# MPU-Power.net
KiCad netlist of a schematic drawn in Altium Designer
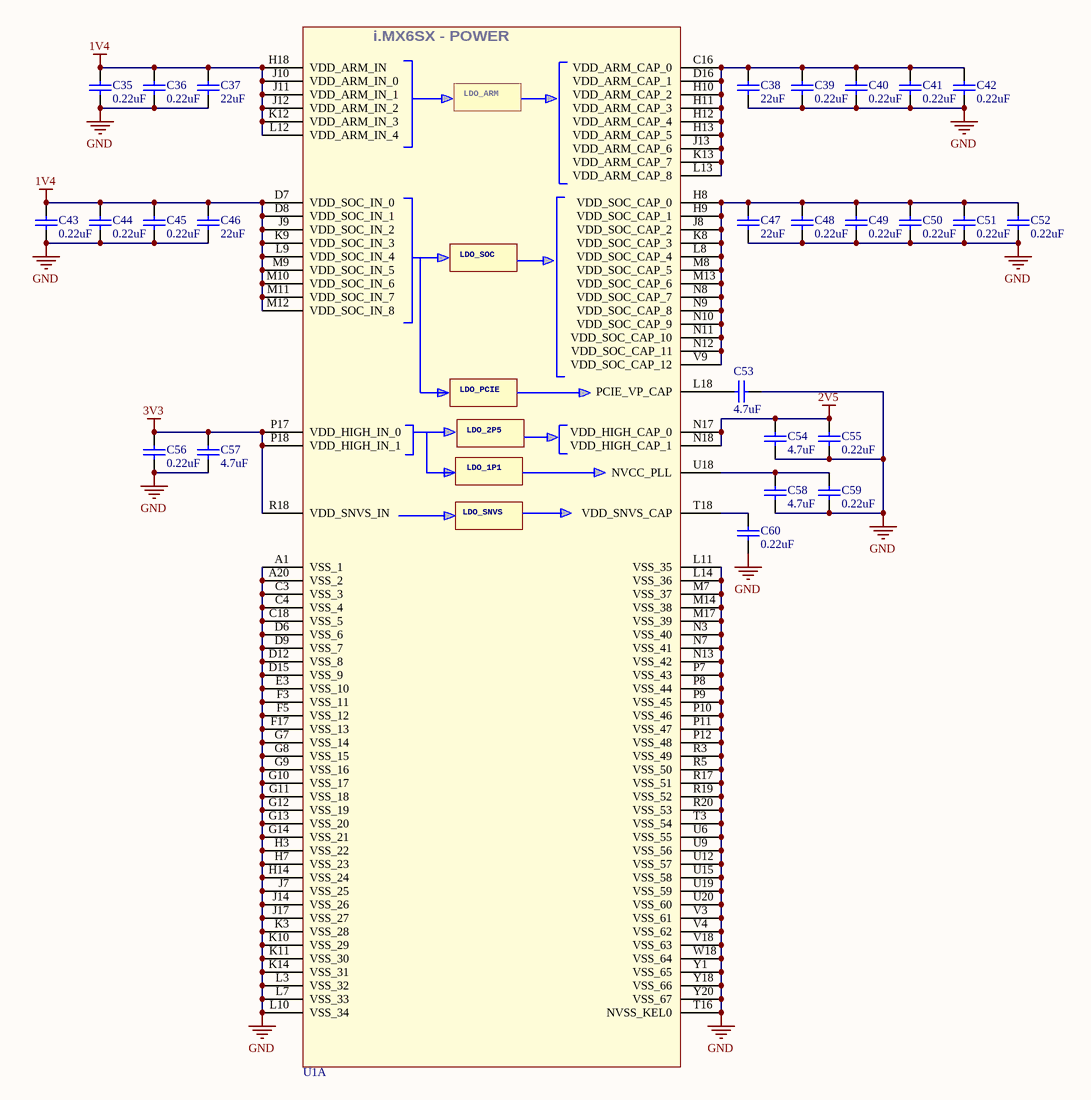
[diagram p0: MPU-Power.SchDoc]

(export (version "E")
  (design (tool "Eeschema 10.0.6"))
  (components
    (comp (ref "C35")
      (value "0.22uF")
      (footprint "C0402[1005X55]")
      (description "0.22uF 6.3V 10% 0402 (1005 Metric)")
      (fields (field (name "PARTNUMBER") "JMK105BJ224KV-F") (field (name "MANUFACTURER") "Taiyo Yuden"))
      (libsource (lib "Capacitors") (part "CAP_0.22uF_6.3V_0402_10%"))
    )
    (comp (ref "C36")
      (value "0.22uF")
      (footprint "C0402[1005X55]")
      (description "0.22uF 6.3V 10% 0402 (1005 Metric)")
      (fields (field (name "PARTNUMBER") "JMK105BJ224KV-F") (field (name "MANUFACTURER") "Taiyo Yuden"))
      (libsource (lib "Capacitors") (part "CAP_0.22uF_6.3V_0402_10%"))
    )
    (comp (ref "C37")
      (value "22uF")
      (footprint "C0603[1608X92]")
      (description "22uF 6.3V 10% 0603 (1608 Metric)")
      (fields (field (name "PARTNUMBER") "GRT188R60J226ME13D") (field (name "MANUFACTURER") "Murata"))
      (libsource (lib "Capacitors") (part "CAP_22uF_6.3V_0603_10%"))
    )
    (comp (ref "C38")
      (value "22uF")
      (footprint "C0603[1608X92]")
      (description "22uF 6.3V 10% 0603 (1608 Metric)")
      (fields (field (name "PARTNUMBER") "GRT188R60J226ME13D") (field (name "MANUFACTURER") "Murata"))
      (libsource (lib "Capacitors") (part "CAP_22uF_6.3V_0603_10%"))
    )
    (comp (ref "C39")
      (value "0.22uF")
      (footprint "C0402[1005X55]")
      (description "0.22uF 6.3V 10% 0402 (1005 Metric)")
      (fields (field (name "PARTNUMBER") "JMK105BJ224KV-F") (field (name "MANUFACTURER") "Taiyo Yuden"))
      (libsource (lib "Capacitors") (part "CAP_0.22uF_6.3V_0402_10%"))
    )
    (comp (ref "C40")
      (value "0.22uF")
      (footprint "C0402[1005X55]")
      (description "0.22uF 6.3V 10% 0402 (1005 Metric)")
      (fields (field (name "PARTNUMBER") "JMK105BJ224KV-F") (field (name "MANUFACTURER") "Taiyo Yuden"))
      (libsource (lib "Capacitors") (part "CAP_0.22uF_6.3V_0402_10%"))
    )
    (comp (ref "C41")
      (value "0.22uF")
      (footprint "C0402[1005X55]")
      (description "0.22uF 6.3V 10% 0402 (1005 Metric)")
      (fields (field (name "PARTNUMBER") "JMK105BJ224KV-F") (field (name "MANUFACTURER") "Taiyo Yuden"))
      (libsource (lib "Capacitors") (part "CAP_0.22uF_6.3V_0402_10%"))
    )
    (comp (ref "C42")
      (value "0.22uF")
      (footprint "C0402[1005X55]")
      (description "0.22uF 6.3V 10% 0402 (1005 Metric)")
      (fields (field (name "PARTNUMBER") "JMK105BJ224KV-F") (field (name "MANUFACTURER") "Taiyo Yuden"))
      (libsource (lib "Capacitors") (part "CAP_0.22uF_6.3V_0402_10%"))
    )
    (comp (ref "C43")
      (value "0.22uF")
      (footprint "C0402[1005X55]")
      (description "0.22uF 6.3V 10% 0402 (1005 Metric)")
      (fields (field (name "PARTNUMBER") "JMK105BJ224KV-F") (field (name "MANUFACTURER") "Taiyo Yuden"))
      (libsource (lib "Capacitors") (part "CAP_0.22uF_6.3V_0402_10%"))
    )
    (comp (ref "C44")
      (value "0.22uF")
      (footprint "C0402[1005X55]")
      (description "0.22uF 6.3V 10% 0402 (1005 Metric)")
      (fields (field (name "PARTNUMBER") "JMK105BJ224KV-F") (field (name "MANUFACTURER") "Taiyo Yuden"))
      (libsource (lib "Capacitors") (part "CAP_0.22uF_6.3V_0402_10%"))
    )
    (comp (ref "C45")
      (value "0.22uF")
      (footprint "C0402[1005X55]")
      (description "0.22uF 6.3V 10% 0402 (1005 Metric)")
      (fields (field (name "PARTNUMBER") "JMK105BJ224KV-F") (field (name "MANUFACTURER") "Taiyo Yuden"))
      (libsource (lib "Capacitors") (part "CAP_0.22uF_6.3V_0402_10%"))
    )
    (comp (ref "C46")
      (value "22uF")
      (footprint "C0603[1608X92]")
      (description "22uF 6.3V 10% 0603 (1608 Metric)")
      (fields (field (name "PARTNUMBER") "GRT188R60J226ME13D") (field (name "MANUFACTURER") "Murata"))
      (libsource (lib "Capacitors") (part "CAP_22uF_6.3V_0603_10%"))
    )
    (comp (ref "C47")
      (value "22uF")
      (footprint "C0603[1608X92]")
      (description "22uF 6.3V 10% 0603 (1608 Metric)")
      (fields (field (name "PARTNUMBER") "GRT188R60J226ME13D") (field (name "MANUFACTURER") "Murata"))
      (libsource (lib "Capacitors") (part "CAP_22uF_6.3V_0603_10%"))
    )
    (comp (ref "C48")
      (value "0.22uF")
      (footprint "C0402[1005X55]")
      (description "0.22uF 6.3V 10% 0402 (1005 Metric)")
      (fields (field (name "PARTNUMBER") "JMK105BJ224KV-F") (field (name "MANUFACTURER") "Taiyo Yuden"))
      (libsource (lib "Capacitors") (part "CAP_0.22uF_6.3V_0402_10%"))
    )
    (comp (ref "C49")
      (value "0.22uF")
      (footprint "C0402[1005X55]")
      (description "0.22uF 6.3V 10% 0402 (1005 Metric)")
      (fields (field (name "PARTNUMBER") "JMK105BJ224KV-F") (field (name "MANUFACTURER") "Taiyo Yuden"))
      (libsource (lib "Capacitors") (part "CAP_0.22uF_6.3V_0402_10%"))
    )
    (comp (ref "C50")
      (value "0.22uF")
      (footprint "C0402[1005X55]")
      (description "0.22uF 6.3V 10% 0402 (1005 Metric)")
      (fields (field (name "PARTNUMBER") "JMK105BJ224KV-F") (field (name "MANUFACTURER") "Taiyo Yuden"))
      (libsource (lib "Capacitors") (part "CAP_0.22uF_6.3V_0402_10%"))
    )
    (comp (ref "C51")
      (value "0.22uF")
      (footprint "C0402[1005X55]")
      (description "0.22uF 6.3V 10% 0402 (1005 Metric)")
      (fields (field (name "PARTNUMBER") "JMK105BJ224KV-F") (field (name "MANUFACTURER") "Taiyo Yuden"))
      (libsource (lib "Capacitors") (part "CAP_0.22uF_6.3V_0402_10%"))
    )
    (comp (ref "C52")
      (value "0.22uF")
      (footprint "C0402[1005X55]")
      (description "0.22uF 6.3V 10% 0402 (1005 Metric)")
      (fields (field (name "PARTNUMBER") "JMK105BJ224KV-F") (field (name "MANUFACTURER") "Taiyo Yuden"))
      (libsource (lib "Capacitors") (part "CAP_0.22uF_6.3V_0402_10%"))
    )
    (comp (ref "C53")
      (value "4.7uF")
      (footprint "C0402[1005X55]")
      (description "4.7uF 6.3V 20% 0402 (1005 Metric)")
      (fields (field (name "PARTNUMBER") "GRM155R60J475ME47D") (field (name "MANUFACTURER") "Murata"))
      (libsource (lib "Capacitors") (part "CAP_4.7uF_6.3V_0402_20%"))
    )
    (comp (ref "C54")
      (value "4.7uF")
      (footprint "C0402[1005X55]")
      (description "4.7uF 6.3V 20% 0402 (1005 Metric)")
      (fields (field (name "PARTNUMBER") "GRM155R60J475ME47D") (field (name "MANUFACTURER") "Murata"))
      (libsource (lib "Capacitors") (part "CAP_4.7uF_6.3V_0402_20%"))
    )
    (comp (ref "C55")
      (value "0.22uF")
      (footprint "C0402[1005X55]")
      (description "0.22uF 6.3V 10% 0402 (1005 Metric)")
      (fields (field (name "PARTNUMBER") "JMK105BJ224KV-F") (field (name "MANUFACTURER") "Taiyo Yuden"))
      (libsource (lib "Capacitors") (part "CAP_0.22uF_6.3V_0402_10%"))
    )
    (comp (ref "C56")
      (value "0.22uF")
      (footprint "C0402[1005X55]")
      (description "0.22uF 6.3V 10% 0402 (1005 Metric)")
      (fields (field (name "PARTNUMBER") "JMK105BJ224KV-F") (field (name "MANUFACTURER") "Taiyo Yuden"))
      (libsource (lib "Capacitors") (part "CAP_0.22uF_6.3V_0402_10%"))
    )
    (comp (ref "C57")
      (value "4.7uF")
      (footprint "C0402[1005X55]")
      (description "4.7uF 6.3V 20% 0402 (1005 Metric)")
      (fields (field (name "PARTNUMBER") "GRM155R60J475ME47D") (field (name "MANUFACTURER") "Murata"))
      (libsource (lib "Capacitors") (part "CAP_4.7uF_6.3V_0402_20%"))
    )
    (comp (ref "C58")
      (value "4.7uF")
      (footprint "C0402[1005X55]")
      (description "4.7uF 6.3V 20% 0402 (1005 Metric)")
      (fields (field (name "PARTNUMBER") "GRM155R60J475ME47D") (field (name "MANUFACTURER") "Murata"))
      (libsource (lib "Capacitors") (part "CAP_4.7uF_6.3V_0402_20%"))
    )
    (comp (ref "C59")
      (value "0.22uF")
      (footprint "C0402[1005X55]")
      (description "0.22uF 6.3V 10% 0402 (1005 Metric)")
      (fields (field (name "PARTNUMBER") "JMK105BJ224KV-F") (field (name "MANUFACTURER") "Taiyo Yuden"))
      (libsource (lib "Capacitors") (part "CAP_0.22uF_6.3V_0402_10%"))
    )
    (comp (ref "C60")
      (value "0.22uF")
      (footprint "C0402[1005X55]")
      (description "0.22uF 6.3V 10% 0402 (1005 Metric)")
      (fields (field (name "PARTNUMBER") "JMK105BJ224KV-F") (field (name "MANUFACTURER") "Taiyo Yuden"))
      (libsource (lib "Capacitors") (part "CAP_0.22uF_6.3V_0402_10%"))
    )
    (comp (ref "U1")
      (value "MCIMX6X3EVO10AB")
      (footprint "BGA-400")
      (description "IC MPU I.MX6SX 1GHZ 400MAPBGA")
      (fields (field (name "MANUFACTURER") "NXP"))
      (libsource (lib "ICs") (part "MCIMX6X3EVO10AB"))
    )
  )
  (nets
    (net (code "1") (name "1V4") (class "Default")
      (node (ref "C35") (pin "2") (pinfunction "2_2") (pintype "passive"))
      (node (ref "C36") (pin "2") (pinfunction "2_2") (pintype "passive"))
      (node (ref "C37") (pin "2") (pinfunction "2_2") (pintype "passive"))
      (node (ref "C43") (pin "2") (pinfunction "2_2") (pintype "passive"))
      (node (ref "C44") (pin "2") (pinfunction "2_2") (pintype "passive"))
      (node (ref "C45") (pin "2") (pinfunction "2_2") (pintype "passive"))
      (node (ref "C46") (pin "2") (pinfunction "2_2") (pintype "passive"))
      (node (ref "U1") (pin "D7") (pinfunction "VDD_SOC_IN_0_D7") (pintype "power_in"))
      (node (ref "U1") (pin "D8") (pinfunction "VDD_SOC_IN_1_D8") (pintype "power_in"))
      (node (ref "U1") (pin "H18") (pinfunction "VDD_ARM_IN_H18") (pintype "power_in"))
      (node (ref "U1") (pin "J10") (pinfunction "VDD_ARM_IN_0_J10") (pintype "power_in"))
      (node (ref "U1") (pin "J11") (pinfunction "VDD_ARM_IN_1_J11") (pintype "power_in"))
      (node (ref "U1") (pin "J12") (pinfunction "VDD_ARM_IN_2_J12") (pintype "power_in"))
      (node (ref "U1") (pin "J9") (pinfunction "VDD_SOC_IN_2_J9") (pintype "power_in"))
      (node (ref "U1") (pin "K12") (pinfunction "VDD_ARM_IN_3_K12") (pintype "power_in"))
      (node (ref "U1") (pin "K9") (pinfunction "VDD_SOC_IN_3_K9") (pintype "power_in"))
      (node (ref "U1") (pin "L12") (pinfunction "VDD_ARM_IN_4_L12") (pintype "power_in"))
      (node (ref "U1") (pin "L9") (pinfunction "VDD_SOC_IN_4_L9") (pintype "power_in"))
      (node (ref "U1") (pin "M10") (pinfunction "VDD_SOC_IN_6_M10") (pintype "power_in"))
      (node (ref "U1") (pin "M11") (pinfunction "VDD_SOC_IN_7_M11") (pintype "power_in"))
      (node (ref "U1") (pin "M12") (pinfunction "VDD_SOC_IN_8_M12") (pintype "power_in"))
      (node (ref "U1") (pin "M9") (pinfunction "VDD_SOC_IN_5_M9") (pintype "power_in"))
    )
    (net (code "2") (name "2V5") (class "Default")
      (node (ref "C54") (pin "2") (pinfunction "2_2") (pintype "passive"))
      (node (ref "C55") (pin "2") (pinfunction "2_2") (pintype "passive"))
      (node (ref "U1") (pin "N17") (pinfunction "VDD_HIGH_CAP_0_N17") (pintype "power_in"))
      (node (ref "U1") (pin "N18") (pinfunction "VDD_HIGH_CAP_1_N18") (pintype "power_in"))
    )
    (net (code "3") (name "3V3") (class "Default")
      (node (ref "C56") (pin "2") (pinfunction "2_2") (pintype "passive"))
      (node (ref "C57") (pin "2") (pinfunction "2_2") (pintype "passive"))
      (node (ref "U1") (pin "P17") (pinfunction "VDD_HIGH_IN_0_P17") (pintype "power_in"))
      (node (ref "U1") (pin "P18") (pinfunction "VDD_HIGH_IN_1_P18") (pintype "power_in"))
      (node (ref "U1") (pin "R18") (pinfunction "VDD_SNVS_IN_R18") (pintype "power_in"))
    )
    (net (code "4") (name "GND") (class "Default")
      (node (ref "C35") (pin "1") (pinfunction "1_1") (pintype "passive"))
      (node (ref "C36") (pin "1") (pinfunction "1_1") (pintype "passive"))
      (node (ref "C37") (pin "1") (pinfunction "1_1") (pintype "passive"))
      (node (ref "C38") (pin "1") (pinfunction "1_1") (pintype "passive"))
      (node (ref "C39") (pin "1") (pinfunction "1_1") (pintype "passive"))
      (node (ref "C40") (pin "1") (pinfunction "1_1") (pintype "passive"))
      (node (ref "C41") (pin "1") (pinfunction "1_1") (pintype "passive"))
      (node (ref "C42") (pin "1") (pinfunction "1_1") (pintype "passive"))
      (node (ref "C43") (pin "1") (pinfunction "1_1") (pintype "passive"))
      (node (ref "C44") (pin "1") (pinfunction "1_1") (pintype "passive"))
      (node (ref "C45") (pin "1") (pinfunction "1_1") (pintype "passive"))
      (node (ref "C46") (pin "1") (pinfunction "1_1") (pintype "passive"))
      (node (ref "C47") (pin "1") (pinfunction "1_1") (pintype "passive"))
      (node (ref "C48") (pin "1") (pinfunction "1_1") (pintype "passive"))
      (node (ref "C49") (pin "1") (pinfunction "1_1") (pintype "passive"))
      (node (ref "C50") (pin "1") (pinfunction "1_1") (pintype "passive"))
      (node (ref "C51") (pin "1") (pinfunction "1_1") (pintype "passive"))
      (node (ref "C52") (pin "1") (pinfunction "1_1") (pintype "passive"))
      (node (ref "C53") (pin "1") (pinfunction "1_1") (pintype "passive"))
      (node (ref "C54") (pin "1") (pinfunction "1_1") (pintype "passive"))
      (node (ref "C55") (pin "1") (pinfunction "1_1") (pintype "passive"))
      (node (ref "C56") (pin "1") (pinfunction "1_1") (pintype "passive"))
      (node (ref "C57") (pin "1") (pinfunction "1_1") (pintype "passive"))
      (node (ref "C58") (pin "1") (pinfunction "1_1") (pintype "passive"))
      (node (ref "C59") (pin "1") (pinfunction "1_1") (pintype "passive"))
      (node (ref "C60") (pin "1") (pinfunction "1_1") (pintype "passive"))
      (node (ref "U1") (pin "A1") (pinfunction "VSS_1_A1") (pintype "power_in"))
      (node (ref "U1") (pin "A20") (pinfunction "VSS_2_A20") (pintype "power_in"))
      (node (ref "U1") (pin "C18") (pinfunction "VSS_5_C18") (pintype "power_in"))
      (node (ref "U1") (pin "C3") (pinfunction "VSS_3_C3") (pintype "power_in"))
      (node (ref "U1") (pin "C4") (pinfunction "VSS_4_C4") (pintype "power_in"))
      (node (ref "U1") (pin "D12") (pinfunction "VSS_8_D12") (pintype "power_in"))
      (node (ref "U1") (pin "D15") (pinfunction "VSS_9_D15") (pintype "power_in"))
      (node (ref "U1") (pin "D6") (pinfunction "VSS_6_D6") (pintype "power_in"))
      (node (ref "U1") (pin "D9") (pinfunction "VSS_7_D9") (pintype "power_in"))
      (node (ref "U1") (pin "E3") (pinfunction "VSS_10_E3") (pintype "power_in"))
      (node (ref "U1") (pin "F17") (pinfunction "VSS_13_F17") (pintype "power_in"))
      (node (ref "U1") (pin "F3") (pinfunction "VSS_11_F3") (pintype "power_in"))
      (node (ref "U1") (pin "F5") (pinfunction "VSS_12_F5") (pintype "power_in"))
      (node (ref "U1") (pin "G10") (pinfunction "VSS_17_G10") (pintype "power_in"))
      (node (ref "U1") (pin "G11") (pinfunction "VSS_18_G11") (pintype "power_in"))
      (node (ref "U1") (pin "G12") (pinfunction "VSS_19_G12") (pintype "power_in"))
      (node (ref "U1") (pin "G13") (pinfunction "VSS_20_G13") (pintype "power_in"))
      (node (ref "U1") (pin "G14") (pinfunction "VSS_21_G14") (pintype "power_in"))
      (node (ref "U1") (pin "G7") (pinfunction "VSS_14_G7") (pintype "power_in"))
      (node (ref "U1") (pin "G8") (pinfunction "VSS_15_G8") (pintype "power_in"))
      (node (ref "U1") (pin "G9") (pinfunction "VSS_16_G9") (pintype "power_in"))
      (node (ref "U1") (pin "H14") (pinfunction "VSS_24_H14") (pintype "power_in"))
      (node (ref "U1") (pin "H3") (pinfunction "VSS_22_H3") (pintype "power_in"))
      (node (ref "U1") (pin "H7") (pinfunction "VSS_23_H7") (pintype "power_in"))
      (node (ref "U1") (pin "J14") (pinfunction "VSS_26_J14") (pintype "power_in"))
      (node (ref "U1") (pin "J17") (pinfunction "VSS_27_J17") (pintype "power_in"))
      (node (ref "U1") (pin "J7") (pinfunction "VSS_25_J7") (pintype "power_in"))
      (node (ref "U1") (pin "K10") (pinfunction "VSS_29_K10") (pintype "power_in"))
      (node (ref "U1") (pin "K11") (pinfunction "VSS_30_K11") (pintype "power_in"))
      (node (ref "U1") (pin "K14") (pinfunction "VSS_31_K14") (pintype "power_in"))
      (node (ref "U1") (pin "K3") (pinfunction "VSS_28_K3") (pintype "power_in"))
      (node (ref "U1") (pin "L10") (pinfunction "VSS_34_L10") (pintype "power_in"))
      (node (ref "U1") (pin "L11") (pinfunction "VSS_35_L11") (pintype "power_in"))
      (node (ref "U1") (pin "L14") (pinfunction "VSS_36_L14") (pintype "power_in"))
      (node (ref "U1") (pin "L3") (pinfunction "VSS_32_L3") (pintype "power_in"))
      (node (ref "U1") (pin "L7") (pinfunction "VSS_33_L7") (pintype "power_in"))
      (node (ref "U1") (pin "M14") (pinfunction "VSS_38_M14") (pintype "power_in"))
      (node (ref "U1") (pin "M17") (pinfunction "VSS_39_M17") (pintype "power_in"))
      (node (ref "U1") (pin "M7") (pinfunction "VSS_37_M7") (pintype "power_in"))
      (node (ref "U1") (pin "N13") (pinfunction "VSS_42_N13") (pintype "power_in"))
      (node (ref "U1") (pin "N3") (pinfunction "VSS_40_N3") (pintype "power_in"))
      (node (ref "U1") (pin "N7") (pinfunction "VSS_41_N7") (pintype "power_in"))
      (node (ref "U1") (pin "P10") (pinfunction "VSS_46_P10") (pintype "power_in"))
      (node (ref "U1") (pin "P11") (pinfunction "VSS_47_P11") (pintype "power_in"))
      (node (ref "U1") (pin "P12") (pinfunction "VSS_48_P12") (pintype "power_in"))
      (node (ref "U1") (pin "P7") (pinfunction "VSS_43_P7") (pintype "power_in"))
      (node (ref "U1") (pin "P8") (pinfunction "VSS_44_P8") (pintype "power_in"))
      (node (ref "U1") (pin "P9") (pinfunction "VSS_45_P9") (pintype "power_in"))
      (node (ref "U1") (pin "R17") (pinfunction "VSS_51_R17") (pintype "power_in"))
      (node (ref "U1") (pin "R19") (pinfunction "VSS_52_R19") (pintype "power_in"))
      (node (ref "U1") (pin "R20") (pinfunction "VSS_53_R20") (pintype "power_in"))
      (node (ref "U1") (pin "R3") (pinfunction "VSS_49_R3") (pintype "power_in"))
      (node (ref "U1") (pin "R5") (pinfunction "VSS_50_R5") (pintype "power_in"))
      (node (ref "U1") (pin "T16") (pinfunction "NVSS_KEL0_T16") (pintype "power_in"))
      (node (ref "U1") (pin "T3") (pinfunction "VSS_54_T3") (pintype "power_in"))
      (node (ref "U1") (pin "U12") (pinfunction "VSS_57_U12") (pintype "power_in"))
      (node (ref "U1") (pin "U15") (pinfunction "VSS_58_U15") (pintype "power_in"))
      (node (ref "U1") (pin "U19") (pinfunction "VSS_59_U19") (pintype "power_in"))
      (node (ref "U1") (pin "U20") (pinfunction "VSS_60_U20") (pintype "power_in"))
      (node (ref "U1") (pin "U6") (pinfunction "VSS_55_U6") (pintype "power_in"))
      (node (ref "U1") (pin "U9") (pinfunction "VSS_56_U9") (pintype "power_in"))
      (node (ref "U1") (pin "V18") (pinfunction "VSS_63_V18") (pintype "power_in"))
      (node (ref "U1") (pin "V3") (pinfunction "VSS_61_V3") (pintype "power_in"))
      (node (ref "U1") (pin "V4") (pinfunction "VSS_62_V4") (pintype "power_in"))
      (node (ref "U1") (pin "W18") (pinfunction "VSS_64_W18") (pintype "power_in"))
      (node (ref "U1") (pin "Y1") (pinfunction "VSS_65_Y1") (pintype "power_in"))
      (node (ref "U1") (pin "Y18") (pinfunction "VSS_66_Y18") (pintype "power_in"))
      (node (ref "U1") (pin "Y20") (pinfunction "VSS_67_Y20") (pintype "power_in"))
    )
    (net (code "5") (name "Net-(U1A-NVCC_PLL)") (class "Default")
      (node (ref "C58") (pin "2") (pinfunction "2_2") (pintype "passive"))
      (node (ref "C59") (pin "2") (pinfunction "2_2") (pintype "passive"))
      (node (ref "U1") (pin "U18") (pinfunction "NVCC_PLL_U18") (pintype "power_in"))
    )
    (net (code "6") (name "Net-(U1A-PCIE_VP_CAP)") (class "Default")
      (node (ref "C53") (pin "2") (pinfunction "2_2") (pintype "passive"))
      (node (ref "U1") (pin "L18") (pinfunction "PCIE_VP_CAP_L18") (pintype "power_in"))
    )
    (net (code "7") (name "Net-(U1A-VDD_ARM_CAP_0)") (class "Default")
      (node (ref "C38") (pin "2") (pinfunction "2_2") (pintype "passive"))
      (node (ref "C39") (pin "2") (pinfunction "2_2") (pintype "passive"))
      (node (ref "C40") (pin "2") (pinfunction "2_2") (pintype "passive"))
      (node (ref "C41") (pin "2") (pinfunction "2_2") (pintype "passive"))
      (node (ref "C42") (pin "2") (pinfunction "2_2") (pintype "passive"))
      (node (ref "U1") (pin "C16") (pinfunction "VDD_ARM_CAP_0_C16") (pintype "power_in"))
      (node (ref "U1") (pin "D16") (pinfunction "VDD_ARM_CAP_1_D16") (pintype "power_in"))
      (node (ref "U1") (pin "H10") (pinfunction "VDD_ARM_CAP_2_H10") (pintype "power_in"))
      (node (ref "U1") (pin "H11") (pinfunction "VDD_ARM_CAP_3_H11") (pintype "power_in"))
      (node (ref "U1") (pin "H12") (pinfunction "VDD_ARM_CAP_4_H12") (pintype "power_in"))
      (node (ref "U1") (pin "H13") (pinfunction "VDD_ARM_CAP_5_H13") (pintype "power_in"))
      (node (ref "U1") (pin "J13") (pinfunction "VDD_ARM_CAP_6_J13") (pintype "power_in"))
      (node (ref "U1") (pin "K13") (pinfunction "VDD_ARM_CAP_7_K13") (pintype "power_in"))
      (node (ref "U1") (pin "L13") (pinfunction "VDD_ARM_CAP_8_L13") (pintype "power_in"))
    )
    (net (code "8") (name "Net-(U1A-VDD_SNVS_CAP)") (class "Default")
      (node (ref "C60") (pin "2") (pinfunction "2_2") (pintype "passive"))
      (node (ref "U1") (pin "T18") (pinfunction "VDD_SNVS_CAP_T18") (pintype "power_in"))
    )
    (net (code "9") (name "Net-(U1A-VDD_SOC_CAP_0)") (class "Default")
      (node (ref "C47") (pin "2") (pinfunction "2_2") (pintype "passive"))
      (node (ref "C48") (pin "2") (pinfunction "2_2") (pintype "passive"))
      (node (ref "C49") (pin "2") (pinfunction "2_2") (pintype "passive"))
      (node (ref "C50") (pin "2") (pinfunction "2_2") (pintype "passive"))
      (node (ref "C51") (pin "2") (pinfunction "2_2") (pintype "passive"))
      (node (ref "C52") (pin "2") (pinfunction "2_2") (pintype "passive"))
      (node (ref "U1") (pin "H8") (pinfunction "VDD_SOC_CAP_0_H8") (pintype "power_in"))
      (node (ref "U1") (pin "H9") (pinfunction "VDD_SOC_CAP_1_H9") (pintype "power_in"))
      (node (ref "U1") (pin "J8") (pinfunction "VDD_SOC_CAP_2_J8") (pintype "power_in"))
      (node (ref "U1") (pin "K8") (pinfunction "VDD_SOC_CAP_3_K8") (pintype "power_in"))
      (node (ref "U1") (pin "L8") (pinfunction "VDD_SOC_CAP_4_L8") (pintype "power_in"))
      (node (ref "U1") (pin "M13") (pinfunction "VDD_SOC_CAP_6_M13") (pintype "power_in"))
      (node (ref "U1") (pin "M8") (pinfunction "VDD_SOC_CAP_5_M8") (pintype "power_in"))
      (node (ref "U1") (pin "N10") (pinfunction "VDD_SOC_CAP_9_N10") (pintype "power_in"))
      (node (ref "U1") (pin "N11") (pinfunction "VDD_SOC_CAP_10_N11") (pintype "power_in"))
      (node (ref "U1") (pin "N12") (pinfunction "VDD_SOC_CAP_11_N12") (pintype "power_in"))
      (node (ref "U1") (pin "N8") (pinfunction "VDD_SOC_CAP_7_N8") (pintype "power_in"))
      (node (ref "U1") (pin "N9") (pinfunction "VDD_SOC_CAP_8_N9") (pintype "power_in"))
      (node (ref "U1") (pin "V9") (pinfunction "VDD_SOC_CAP_12_V9") (pintype "power_in"))
    )
  )
)
